# Connect.net
KiCad netlist of a schematic drawn in Altium Designer
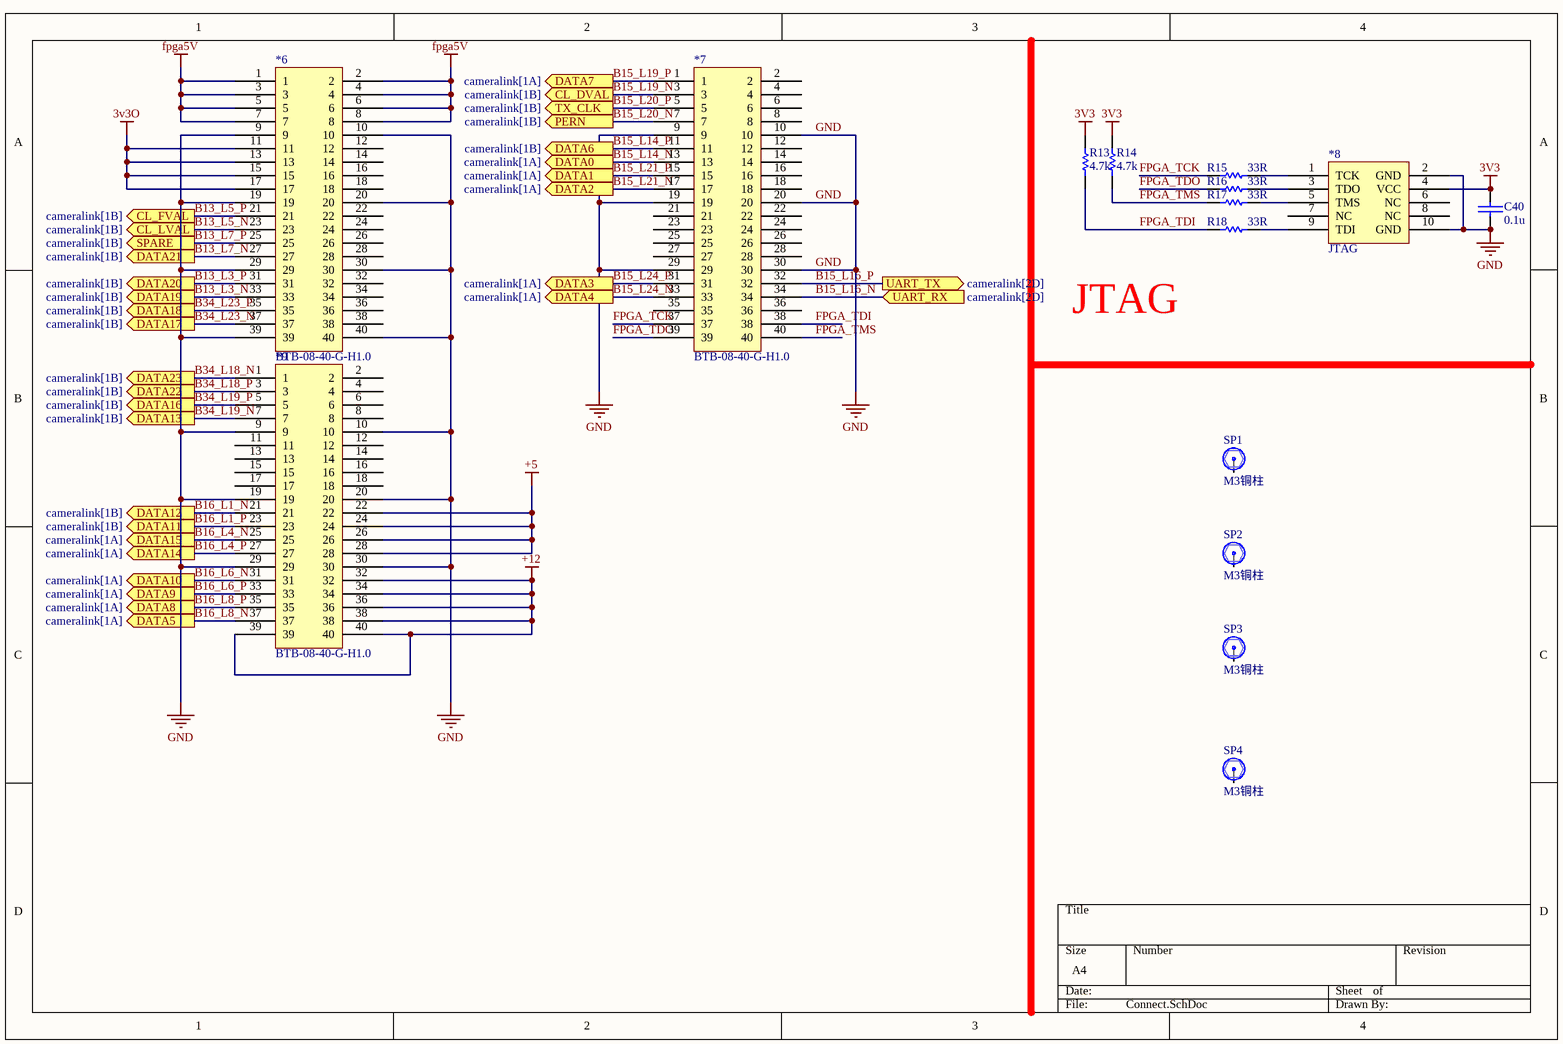
[diagram p0: Connect.SchDoc]

(export (version "E")
  (design (tool "Eeschema 10.0.6"))
  (components
    (comp (ref "*6")
      (value "BTB-08-40-G-H1.0")
      (footprint "BTB-08-40-M-H1.0")
      (libsource (lib "0.04连接器") (part "BTB-08-40-G-H1.0"))
    )
    (comp (ref "*7")
      (value "BTB-08-40-G-H1.0")
      (footprint "BTB-08-40-M-H1.0")
      (libsource (lib "0.04连接器") (part "BTB-08-40-G-H1.0"))
    )
    (comp (ref "*8") (value "JTAG") (footprint "JTAG") (libsource (lib "0.05-mylib") (part "JTAG")))
    (comp (ref "*9")
      (value "BTB-08-40-G-H1.0")
      (footprint "BTB-08-40-M-H1.0")
      (libsource (lib "0.04连接器") (part "BTB-08-40-G-H1.0"))
    )
    (comp (ref "C40")
      (value "0.1u")
      (footprint "0603C")
      (description "无极性电容")
      (libsource (lib "1.00-阻容感") (part "CAP"))
    )
    (comp (ref "R13")
      (value "4.7k")
      (footprint "0603R")
      (description "电阻")
      (libsource (lib "1.00-阻容感") (part "RES"))
    )
    (comp (ref "R14")
      (value "4.7k")
      (footprint "0603R")
      (description "电阻")
      (libsource (lib "1.00-阻容感") (part "RES"))
    )
    (comp (ref "R15")
      (value "33R")
      (footprint "0603R")
      (description "电阻")
      (libsource (lib "1.00-阻容感") (part "RES"))
    )
    (comp (ref "R16")
      (value "33R")
      (footprint "0603R")
      (description "电阻")
      (libsource (lib "1.00-阻容感") (part "RES"))
    )
    (comp (ref "R17")
      (value "33R")
      (footprint "0603R")
      (description "电阻")
      (libsource (lib "1.00-阻容感") (part "RES"))
    )
    (comp (ref "R18")
      (value "33R")
      (footprint "0603R")
      (description "电阻")
      (libsource (lib "1.00-阻容感") (part "RES"))
    )
    (comp (ref "SP1")
      (value "M3铜柱")
      (footprint "M3x4_N")
      (description "铜柱")
      (fields (field (name "版权归属") "封装库来自淘宝 ID：黄晶宝石"))
      (libsource (lib "9.09-固定柱") (part "铜柱大焊盘"))
    )
    (comp (ref "SP2")
      (value "M3铜柱")
      (footprint "M3x4_N")
      (description "铜柱")
      (fields (field (name "版权归属") "封装库来自淘宝 ID：黄晶宝石"))
      (libsource (lib "9.09-固定柱") (part "铜柱大焊盘"))
    )
    (comp (ref "SP3")
      (value "M3铜柱")
      (footprint "M3x4_N")
      (description "铜柱")
      (fields (field (name "版权归属") "封装库来自淘宝 ID：黄晶宝石"))
      (libsource (lib "9.09-固定柱") (part "铜柱大焊盘"))
    )
    (comp (ref "SP4")
      (value "M3铜柱")
      (footprint "M3x4_N")
      (description "铜柱")
      (fields (field (name "版权归属") "封装库来自淘宝 ID：黄晶宝石"))
      (libsource (lib "9.09-固定柱") (part "铜柱大焊盘"))
    )
  )
  (nets
    (net (code "1") (name "+5") (class "Default")
      (node (ref "*9") (pin "22") (pinfunction "22_22") (pintype "passive"))
      (node (ref "*9") (pin "24") (pinfunction "24_24") (pintype "passive"))
      (node (ref "*9") (pin "26") (pinfunction "26_26") (pintype "passive"))
      (node (ref "*9") (pin "28") (pinfunction "28_28") (pintype "passive"))
    )
    (net (code "2") (name "+12") (class "Default")
      (node (ref "*9") (pin "32") (pinfunction "32_32") (pintype "passive"))
      (node (ref "*9") (pin "34") (pinfunction "34_34") (pintype "passive"))
      (node (ref "*9") (pin "36") (pinfunction "36_36") (pintype "passive"))
      (node (ref "*9") (pin "38") (pinfunction "38_38") (pintype "passive"))
      (node (ref "*9") (pin "39") (pinfunction "39_39") (pintype "passive"))
      (node (ref "*9") (pin "40") (pinfunction "40_40") (pintype "passive"))
    )
    (net (code "3") (name "/B13_L3_N") (class "Default")
      (node (ref "*6") (pin "33") (pinfunction "33_33") (pintype "passive"))
    )
    (net (code "4") (name "/B13_L3_P") (class "Default")
      (node (ref "*6") (pin "31") (pinfunction "31_31") (pintype "passive"))
    )
    (net (code "5") (name "/B13_L5_N") (class "Default")
      (node (ref "*6") (pin "23") (pinfunction "23_23") (pintype "passive"))
    )
    (net (code "6") (name "/B13_L5_P") (class "Default")
      (node (ref "*6") (pin "21") (pinfunction "21_21") (pintype "passive"))
    )
    (net (code "7") (name "/B13_L7_N") (class "Default")
      (node (ref "*6") (pin "27") (pinfunction "27_27") (pintype "passive"))
    )
    (net (code "8") (name "/B13_L7_P") (class "Default")
      (node (ref "*6") (pin "25") (pinfunction "25_25") (pintype "passive"))
    )
    (net (code "9") (name "/B15_L14_N") (class "Default")
      (node (ref "*7") (pin "13") (pinfunction "13_13") (pintype "passive"))
    )
    (net (code "10") (name "/B15_L14_P") (class "Default")
      (node (ref "*7") (pin "11") (pinfunction "11_11") (pintype "passive"))
    )
    (net (code "11") (name "/B15_L16_N") (class "Default")
      (node (ref "*7") (pin "34") (pinfunction "34_34") (pintype "passive"))
    )
    (net (code "12") (name "/B15_L16_P") (class "Default")
      (node (ref "*7") (pin "32") (pinfunction "32_32") (pintype "passive"))
    )
    (net (code "13") (name "/B15_L19_N") (class "Default")
      (node (ref "*7") (pin "3") (pinfunction "3_3") (pintype "passive"))
    )
    (net (code "14") (name "/B15_L19_P") (class "Default")
      (node (ref "*7") (pin "1") (pinfunction "1_1") (pintype "passive"))
    )
    (net (code "15") (name "/B15_L20_N") (class "Default")
      (node (ref "*7") (pin "7") (pinfunction "7_7") (pintype "passive"))
    )
    (net (code "16") (name "/B15_L20_P") (class "Default")
      (node (ref "*7") (pin "5") (pinfunction "5_5") (pintype "passive"))
    )
    (net (code "17") (name "/B15_L21_N") (class "Default")
      (node (ref "*7") (pin "17") (pinfunction "17_17") (pintype "passive"))
    )
    (net (code "18") (name "/B15_L21_P") (class "Default")
      (node (ref "*7") (pin "15") (pinfunction "15_15") (pintype "passive"))
    )
    (net (code "19") (name "/B15_L24_N") (class "Default")
      (node (ref "*7") (pin "33") (pinfunction "33_33") (pintype "passive"))
    )
    (net (code "20") (name "/B15_L24_P") (class "Default")
      (node (ref "*7") (pin "31") (pinfunction "31_31") (pintype "passive"))
    )
    (net (code "21") (name "/B16_L1_N") (class "Default")
      (node (ref "*9") (pin "21") (pinfunction "21_21") (pintype "passive"))
    )
    (net (code "22") (name "/B16_L1_P") (class "Default")
      (node (ref "*9") (pin "23") (pinfunction "23_23") (pintype "passive"))
    )
    (net (code "23") (name "/B16_L4_N") (class "Default")
      (node (ref "*9") (pin "25") (pinfunction "25_25") (pintype "passive"))
    )
    (net (code "24") (name "/B16_L4_P") (class "Default")
      (node (ref "*9") (pin "27") (pinfunction "27_27") (pintype "passive"))
    )
    (net (code "25") (name "/B16_L6_N") (class "Default")
      (node (ref "*9") (pin "31") (pinfunction "31_31") (pintype "passive"))
    )
    (net (code "26") (name "/B16_L6_P") (class "Default")
      (node (ref "*9") (pin "33") (pinfunction "33_33") (pintype "passive"))
    )
    (net (code "27") (name "/B16_L8_N") (class "Default")
      (node (ref "*9") (pin "37") (pinfunction "37_37") (pintype "passive"))
    )
    (net (code "28") (name "/B16_L8_P") (class "Default")
      (node (ref "*9") (pin "35") (pinfunction "35_35") (pintype "passive"))
    )
    (net (code "29") (name "/B34_L18_N") (class "Default")
      (node (ref "*9") (pin "1") (pinfunction "1_1") (pintype "passive"))
    )
    (net (code "30") (name "/B34_L18_P") (class "Default")
      (node (ref "*9") (pin "3") (pinfunction "3_3") (pintype "passive"))
    )
    (net (code "31") (name "/B34_L19_N") (class "Default")
      (node (ref "*9") (pin "7") (pinfunction "7_7") (pintype "passive"))
    )
    (net (code "32") (name "/B34_L19_P") (class "Default")
      (node (ref "*9") (pin "5") (pinfunction "5_5") (pintype "passive"))
    )
    (net (code "33") (name "/B34_L23_N") (class "Default")
      (node (ref "*6") (pin "37") (pinfunction "37_37") (pintype "passive"))
    )
    (net (code "34") (name "/B34_L23_P") (class "Default")
      (node (ref "*6") (pin "35") (pinfunction "35_35") (pintype "passive"))
    )
    (net (code "35") (name "/FPGA_TCK") (class "Default")
      (node (ref "*7") (pin "37") (pinfunction "37_37") (pintype "passive"))
      (node (ref "R15") (pin "1") (pinfunction "1_1") (pintype "passive"))
    )
    (net (code "36") (name "/FPGA_TDI") (class "Default")
      (node (ref "*7") (pin "38") (pinfunction "38_38") (pintype "passive"))
      (node (ref "R13") (pin "1") (pinfunction "1_1") (pintype "passive"))
      (node (ref "R18") (pin "1") (pinfunction "1_1") (pintype "passive"))
    )
    (net (code "37") (name "/FPGA_TDO") (class "Default")
      (node (ref "*7") (pin "39") (pinfunction "39_39") (pintype "passive"))
      (node (ref "R16") (pin "1") (pinfunction "1_1") (pintype "passive"))
    )
    (net (code "38") (name "/FPGA_TMS") (class "Default")
      (node (ref "*7") (pin "40") (pinfunction "40_40") (pintype "passive"))
      (node (ref "R14") (pin "1") (pinfunction "1_1") (pintype "passive"))
      (node (ref "R17") (pin "1") (pinfunction "1_1") (pintype "passive"))
    )
    (net (code "39") (name "3V3") (class "Default")
      (node (ref "*8") (pin "4") (pinfunction "VCC_4") (pintype "passive"))
      (node (ref "C40") (pin "2") (pinfunction "2_2") (pintype "passive"))
      (node (ref "R13") (pin "2") (pinfunction "2_2") (pintype "passive"))
      (node (ref "R14") (pin "2") (pinfunction "2_2") (pintype "passive"))
    )
    (net (code "40") (name "3v3O") (class "Default")
      (node (ref "*6") (pin "11") (pinfunction "11_11") (pintype "passive"))
      (node (ref "*6") (pin "13") (pinfunction "13_13") (pintype "passive"))
      (node (ref "*6") (pin "15") (pinfunction "15_15") (pintype "passive"))
      (node (ref "*6") (pin "17") (pinfunction "17_17") (pintype "passive"))
    )
    (net (code "41") (name "GND") (class "Default")
      (node (ref "*6") (pin "10") (pinfunction "10_10") (pintype "passive"))
      (node (ref "*6") (pin "19") (pinfunction "19_19") (pintype "passive"))
      (node (ref "*6") (pin "20") (pinfunction "20_20") (pintype "passive"))
      (node (ref "*6") (pin "29") (pinfunction "29_29") (pintype "passive"))
      (node (ref "*6") (pin "30") (pinfunction "30_30") (pintype "passive"))
      (node (ref "*6") (pin "39") (pinfunction "39_39") (pintype "passive"))
      (node (ref "*6") (pin "40") (pinfunction "40_40") (pintype "passive"))
      (node (ref "*6") (pin "9") (pinfunction "9_9") (pintype "passive"))
      (node (ref "*7") (pin "10") (pinfunction "10_10") (pintype "passive"))
      (node (ref "*7") (pin "19") (pinfunction "19_19") (pintype "passive"))
      (node (ref "*7") (pin "20") (pinfunction "20_20") (pintype "passive"))
      (node (ref "*7") (pin "29") (pinfunction "29_29") (pintype "passive"))
      (node (ref "*7") (pin "30") (pinfunction "30_30") (pintype "passive"))
      (node (ref "*7") (pin "9") (pinfunction "9_9") (pintype "passive"))
      (node (ref "*8") (pin "10") (pinfunction "GND_10") (pintype "passive"))
      (node (ref "*8") (pin "2") (pinfunction "GND_2") (pintype "passive"))
      (node (ref "*9") (pin "10") (pinfunction "10_10") (pintype "passive"))
      (node (ref "*9") (pin "19") (pinfunction "19_19") (pintype "passive"))
      (node (ref "*9") (pin "20") (pinfunction "20_20") (pintype "passive"))
      (node (ref "*9") (pin "29") (pinfunction "29_29") (pintype "passive"))
      (node (ref "*9") (pin "30") (pinfunction "30_30") (pintype "passive"))
      (node (ref "*9") (pin "9") (pinfunction "9_9") (pintype "passive"))
      (node (ref "C40") (pin "1") (pinfunction "1_1") (pintype "passive"))
    )
    (net (code "42") (name "Net-(*8-TCK)") (class "Default")
      (node (ref "*8") (pin "1") (pinfunction "TCK_1") (pintype "passive"))
      (node (ref "R15") (pin "2") (pinfunction "2_2") (pintype "passive"))
    )
    (net (code "43") (name "Net-(*8-TDI)") (class "Default")
      (node (ref "*8") (pin "9") (pinfunction "TDI_9") (pintype "passive"))
      (node (ref "R18") (pin "2") (pinfunction "2_2") (pintype "passive"))
    )
    (net (code "44") (name "Net-(*8-TDO)") (class "Default")
      (node (ref "*8") (pin "3") (pinfunction "TDO_3") (pintype "passive"))
      (node (ref "R16") (pin "2") (pinfunction "2_2") (pintype "passive"))
    )
    (net (code "45") (name "Net-(*8-TMS)") (class "Default")
      (node (ref "*8") (pin "5") (pinfunction "TMS_5") (pintype "passive"))
      (node (ref "R17") (pin "2") (pinfunction "2_2") (pintype "passive"))
    )
    (net (code "46") (name "fpga5V") (class "Default")
      (node (ref "*6") (pin "1") (pinfunction "1_1") (pintype "passive"))
      (node (ref "*6") (pin "2") (pinfunction "2_2") (pintype "passive"))
      (node (ref "*6") (pin "3") (pinfunction "3_3") (pintype "passive"))
      (node (ref "*6") (pin "4") (pinfunction "4_4") (pintype "passive"))
      (node (ref "*6") (pin "5") (pinfunction "5_5") (pintype "passive"))
      (node (ref "*6") (pin "6") (pinfunction "6_6") (pintype "passive"))
      (node (ref "*6") (pin "7") (pinfunction "7_7") (pintype "passive"))
      (node (ref "*6") (pin "8") (pinfunction "8_8") (pintype "passive"))
    )
    (net (code "47") (name "unconnected-(*6-Pad12)") (class "Default")
      (node (ref "*6") (pin "12") (pinfunction "12_12") (pintype "passive"))
    )
    (net (code "48") (name "unconnected-(*6-Pad14)") (class "Default")
      (node (ref "*6") (pin "14") (pinfunction "14_14") (pintype "passive"))
    )
    (net (code "49") (name "unconnected-(*6-Pad16)") (class "Default")
      (node (ref "*6") (pin "16") (pinfunction "16_16") (pintype "passive"))
    )
    (net (code "50") (name "unconnected-(*6-Pad18)") (class "Default")
      (node (ref "*6") (pin "18") (pinfunction "18_18") (pintype "passive"))
    )
    (net (code "51") (name "unconnected-(*6-Pad22)") (class "Default")
      (node (ref "*6") (pin "22") (pinfunction "22_22") (pintype "passive"))
    )
    (net (code "52") (name "unconnected-(*6-Pad24)") (class "Default")
      (node (ref "*6") (pin "24") (pinfunction "24_24") (pintype "passive"))
    )
    (net (code "53") (name "unconnected-(*6-Pad26)") (class "Default")
      (node (ref "*6") (pin "26") (pinfunction "26_26") (pintype "passive"))
    )
    (net (code "54") (name "unconnected-(*6-Pad28)") (class "Default")
      (node (ref "*6") (pin "28") (pinfunction "28_28") (pintype "passive"))
    )
    (net (code "55") (name "unconnected-(*6-Pad32)") (class "Default")
      (node (ref "*6") (pin "32") (pinfunction "32_32") (pintype "passive"))
    )
    (net (code "56") (name "unconnected-(*6-Pad34)") (class "Default")
      (node (ref "*6") (pin "34") (pinfunction "34_34") (pintype "passive"))
    )
    (net (code "57") (name "unconnected-(*6-Pad36)") (class "Default")
      (node (ref "*6") (pin "36") (pinfunction "36_36") (pintype "passive"))
    )
    (net (code "58") (name "unconnected-(*6-Pad38)") (class "Default")
      (node (ref "*6") (pin "38") (pinfunction "38_38") (pintype "passive"))
    )
    (net (code "59") (name "unconnected-(*7-Pad2)") (class "Default")
      (node (ref "*7") (pin "2") (pinfunction "2_2") (pintype "passive"))
    )
    (net (code "60") (name "unconnected-(*7-Pad4)") (class "Default")
      (node (ref "*7") (pin "4") (pinfunction "4_4") (pintype "passive"))
    )
    (net (code "61") (name "unconnected-(*7-Pad6)") (class "Default")
      (node (ref "*7") (pin "6") (pinfunction "6_6") (pintype "passive"))
    )
    (net (code "62") (name "unconnected-(*7-Pad8)") (class "Default")
      (node (ref "*7") (pin "8") (pinfunction "8_8") (pintype "passive"))
    )
    (net (code "63") (name "unconnected-(*7-Pad12)") (class "Default")
      (node (ref "*7") (pin "12") (pinfunction "12_12") (pintype "passive"))
    )
    (net (code "64") (name "unconnected-(*7-Pad14)") (class "Default")
      (node (ref "*7") (pin "14") (pinfunction "14_14") (pintype "passive"))
    )
    (net (code "65") (name "unconnected-(*7-Pad16)") (class "Default")
      (node (ref "*7") (pin "16") (pinfunction "16_16") (pintype "passive"))
    )
    (net (code "66") (name "unconnected-(*7-Pad18)") (class "Default")
      (node (ref "*7") (pin "18") (pinfunction "18_18") (pintype "passive"))
    )
    (net (code "67") (name "unconnected-(*7-Pad21)") (class "Default")
      (node (ref "*7") (pin "21") (pinfunction "21_21") (pintype "passive"))
    )
    (net (code "68") (name "unconnected-(*7-Pad22)") (class "Default")
      (node (ref "*7") (pin "22") (pinfunction "22_22") (pintype "passive"))
    )
    (net (code "69") (name "unconnected-(*7-Pad23)") (class "Default")
      (node (ref "*7") (pin "23") (pinfunction "23_23") (pintype "passive"))
    )
    (net (code "70") (name "unconnected-(*7-Pad24)") (class "Default")
      (node (ref "*7") (pin "24") (pinfunction "24_24") (pintype "passive"))
    )
    (net (code "71") (name "unconnected-(*7-Pad25)") (class "Default")
      (node (ref "*7") (pin "25") (pinfunction "25_25") (pintype "passive"))
    )
    (net (code "72") (name "unconnected-(*7-Pad26)") (class "Default")
      (node (ref "*7") (pin "26") (pinfunction "26_26") (pintype "passive"))
    )
    (net (code "73") (name "unconnected-(*7-Pad27)") (class "Default")
      (node (ref "*7") (pin "27") (pinfunction "27_27") (pintype "passive"))
    )
    (net (code "74") (name "unconnected-(*7-Pad28)") (class "Default")
      (node (ref "*7") (pin "28") (pinfunction "28_28") (pintype "passive"))
    )
    (net (code "75") (name "unconnected-(*7-Pad35)") (class "Default")
      (node (ref "*7") (pin "35") (pinfunction "35_35") (pintype "passive"))
    )
    (net (code "76") (name "unconnected-(*7-Pad36)") (class "Default")
      (node (ref "*7") (pin "36") (pinfunction "36_36") (pintype "passive"))
    )
    (net (code "77") (name "unconnected-(*8-NC-Pad6)") (class "Default")
      (node (ref "*8") (pin "6") (pinfunction "NC_6") (pintype "passive"))
    )
    (net (code "78") (name "unconnected-(*8-NC-Pad7)") (class "Default")
      (node (ref "*8") (pin "7") (pinfunction "NC_7") (pintype "passive"))
    )
    (net (code "79") (name "unconnected-(*8-NC-Pad8)") (class "Default")
      (node (ref "*8") (pin "8") (pinfunction "NC_8") (pintype "passive"))
    )
    (net (code "80") (name "unconnected-(*9-Pad2)") (class "Default")
      (node (ref "*9") (pin "2") (pinfunction "2_2") (pintype "passive"))
    )
    (net (code "81") (name "unconnected-(*9-Pad4)") (class "Default")
      (node (ref "*9") (pin "4") (pinfunction "4_4") (pintype "passive"))
    )
    (net (code "82") (name "unconnected-(*9-Pad6)") (class "Default")
      (node (ref "*9") (pin "6") (pinfunction "6_6") (pintype "passive"))
    )
    (net (code "83") (name "unconnected-(*9-Pad8)") (class "Default")
      (node (ref "*9") (pin "8") (pinfunction "8_8") (pintype "passive"))
    )
    (net (code "84") (name "unconnected-(*9-Pad11)") (class "Default")
      (node (ref "*9") (pin "11") (pinfunction "11_11") (pintype "passive"))
    )
    (net (code "85") (name "unconnected-(*9-Pad12)") (class "Default")
      (node (ref "*9") (pin "12") (pinfunction "12_12") (pintype "passive"))
    )
    (net (code "86") (name "unconnected-(*9-Pad13)") (class "Default")
      (node (ref "*9") (pin "13") (pinfunction "13_13") (pintype "passive"))
    )
    (net (code "87") (name "unconnected-(*9-Pad14)") (class "Default")
      (node (ref "*9") (pin "14") (pinfunction "14_14") (pintype "passive"))
    )
    (net (code "88") (name "unconnected-(*9-Pad15)") (class "Default")
      (node (ref "*9") (pin "15") (pinfunction "15_15") (pintype "passive"))
    )
    (net (code "89") (name "unconnected-(*9-Pad16)") (class "Default")
      (node (ref "*9") (pin "16") (pinfunction "16_16") (pintype "passive"))
    )
    (net (code "90") (name "unconnected-(*9-Pad17)") (class "Default")
      (node (ref "*9") (pin "17") (pinfunction "17_17") (pintype "passive"))
    )
    (net (code "91") (name "unconnected-(*9-Pad18)") (class "Default")
      (node (ref "*9") (pin "18") (pinfunction "18_18") (pintype "passive"))
    )
    (net (code "92") (name "unconnected-(SP1-Pad1)") (class "Default")
      (node (ref "SP1") (pin "1") (pinfunction "1_1") (pintype "passive"))
    )
    (net (code "93") (name "unconnected-(SP2-Pad1)") (class "Default")
      (node (ref "SP2") (pin "1") (pinfunction "1_1") (pintype "passive"))
    )
    (net (code "94") (name "unconnected-(SP3-Pad1)") (class "Default")
      (node (ref "SP3") (pin "1") (pinfunction "1_1") (pintype "passive"))
    )
    (net (code "95") (name "unconnected-(SP4-Pad1)") (class "Default")
      (node (ref "SP4") (pin "1") (pinfunction "1_1") (pintype "passive"))
    )
  )
)
